# beatrix_A_v1.net
KiCad netlist of a schematic drawn in EAGLE
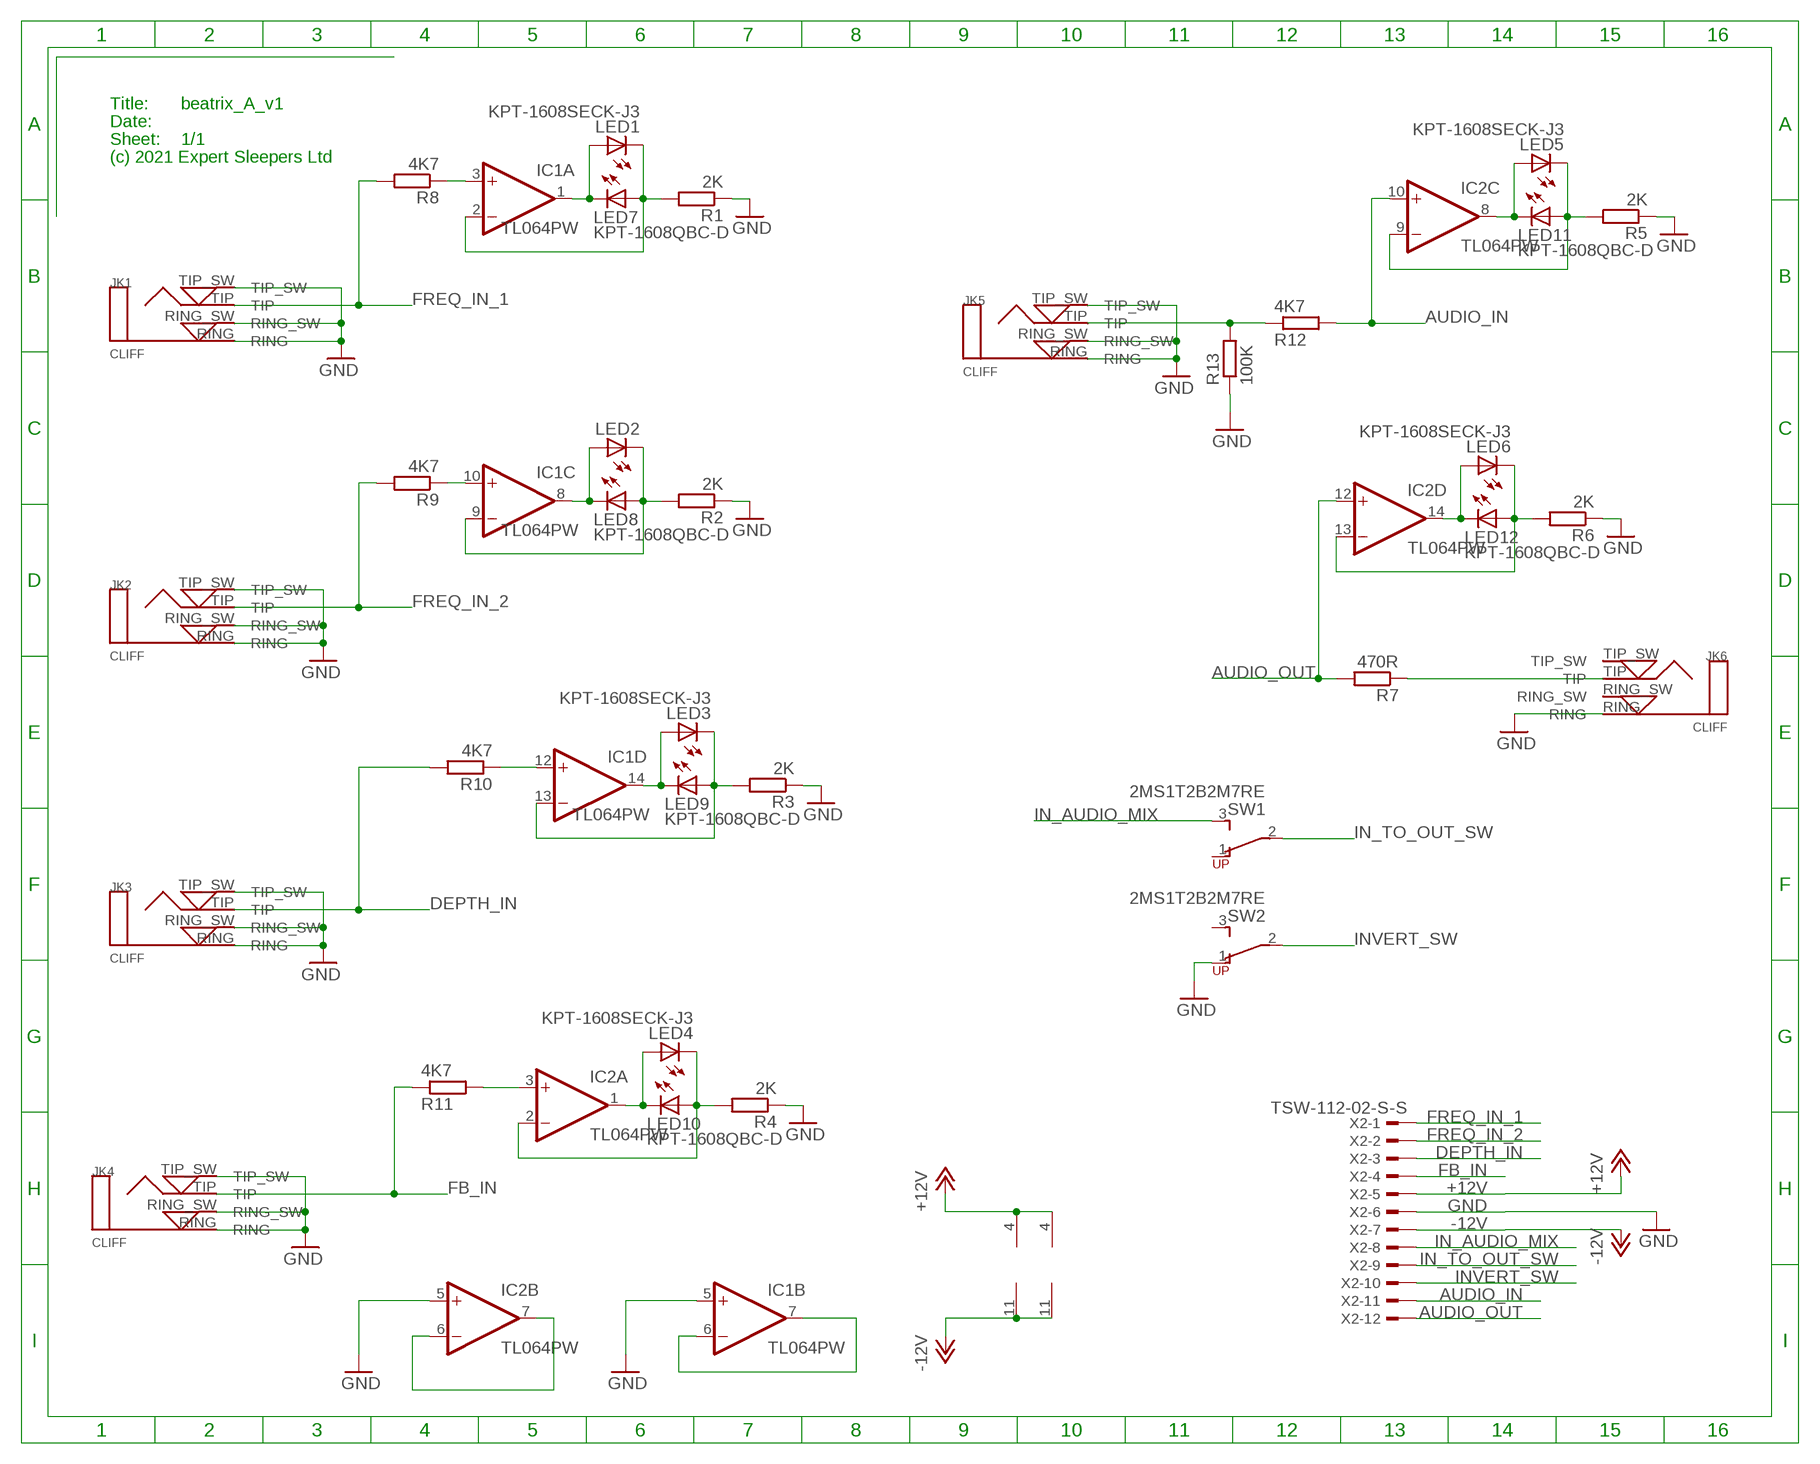
[diagram p0: schematic, sheet 1]

(export (version "E")
  (design (tool "Eeschema 10.0.6"))
  (components
    (comp (ref "IC1")
      (value "TL064PW")
      (footprint "eagle-import:PW_R-PDSO-G14")
      (libsource (lib "eagle-import") (part "TL074PW"))
    )
    (comp (ref "IC2")
      (value "TL064PW")
      (footprint "eagle-import:PW_R-PDSO-G14")
      (libsource (lib "eagle-import") (part "TL074PW"))
    )
    (comp (ref "JK1")
      (value "CLIFF")
      (footprint "eagle-import:CLIFF3.5MMPCB")
      (libsource (lib "eagle-import") (part "CLIFF3.5MM_PCB_SW_JK"))
    )
    (comp (ref "JK2")
      (value "CLIFF")
      (footprint "eagle-import:CLIFF3.5MMPCB")
      (libsource (lib "eagle-import") (part "CLIFF3.5MM_PCB_SW_JK"))
    )
    (comp (ref "JK3")
      (value "CLIFF")
      (footprint "eagle-import:CLIFF3.5MMPCB")
      (libsource (lib "eagle-import") (part "CLIFF3.5MM_PCB_SW_JK"))
    )
    (comp (ref "JK4")
      (value "CLIFF")
      (footprint "eagle-import:CLIFF3.5MMPCB")
      (libsource (lib "eagle-import") (part "CLIFF3.5MM_PCB_SW_JK"))
    )
    (comp (ref "JK5")
      (value "CLIFF")
      (footprint "eagle-import:CLIFF3.5MMPCB")
      (libsource (lib "eagle-import") (part "CLIFF3.5MM_PCB_SW_JK"))
    )
    (comp (ref "JK6")
      (value "CLIFF")
      (footprint "eagle-import:CLIFF3.5MMPCB")
      (libsource (lib "eagle-import") (part "CLIFF3.5MM_PCB_SW_JK"))
    )
    (comp (ref "LED1")
      (value "KPT-1608SECK-J3")
      (footprint "eagle-import:CHIPLED_0603_LEFT")
      (libsource (lib "eagle-import") (part "KPT-1608SECK-J3"))
    )
    (comp (ref "LED2")
      (value "KPT-1608SECK-J3")
      (footprint "eagle-import:CHIPLED_0603_LEFT")
      (libsource (lib "eagle-import") (part "KPT-1608SECK-J3"))
    )
    (comp (ref "LED3")
      (value "KPT-1608SECK-J3")
      (footprint "eagle-import:CHIPLED_0603_LEFT")
      (libsource (lib "eagle-import") (part "KPT-1608SECK-J3"))
    )
    (comp (ref "LED4")
      (value "KPT-1608SECK-J3")
      (footprint "eagle-import:CHIPLED_0603_LEFT")
      (libsource (lib "eagle-import") (part "KPT-1608SECK-J3"))
    )
    (comp (ref "LED5")
      (value "KPT-1608SECK-J3")
      (footprint "eagle-import:CHIPLED_0603_LEFT")
      (libsource (lib "eagle-import") (part "KPT-1608SECK-J3"))
    )
    (comp (ref "LED6")
      (value "KPT-1608SECK-J3")
      (footprint "eagle-import:CHIPLED_0603_LEFT")
      (libsource (lib "eagle-import") (part "KPT-1608SECK-J3"))
    )
    (comp (ref "LED7")
      (value "KPT-1608QBC-D")
      (footprint "eagle-import:CHIPLED_0603_RIGHT")
      (libsource (lib "eagle-import") (part "KPT-1608QBC-D"))
    )
    (comp (ref "LED8")
      (value "KPT-1608QBC-D")
      (footprint "eagle-import:CHIPLED_0603_RIGHT")
      (libsource (lib "eagle-import") (part "KPT-1608QBC-D"))
    )
    (comp (ref "LED9")
      (value "KPT-1608QBC-D")
      (footprint "eagle-import:CHIPLED_0603_RIGHT")
      (libsource (lib "eagle-import") (part "KPT-1608QBC-D"))
    )
    (comp (ref "LED10")
      (value "KPT-1608QBC-D")
      (footprint "eagle-import:CHIPLED_0603_RIGHT")
      (libsource (lib "eagle-import") (part "KPT-1608QBC-D"))
    )
    (comp (ref "LED11")
      (value "KPT-1608QBC-D")
      (footprint "eagle-import:CHIPLED_0603_RIGHT")
      (libsource (lib "eagle-import") (part "KPT-1608QBC-D"))
    )
    (comp (ref "LED12")
      (value "KPT-1608QBC-D")
      (footprint "eagle-import:CHIPLED_0603_RIGHT")
      (libsource (lib "eagle-import") (part "KPT-1608QBC-D"))
    )
    (comp (ref "R1")
      (value "2K")
      (footprint "eagle-import:R1206")
      (libsource (lib "eagle-import") (part "R-EU_R1206"))
    )
    (comp (ref "R2")
      (value "2K")
      (footprint "eagle-import:R1206")
      (libsource (lib "eagle-import") (part "R-EU_R1206"))
    )
    (comp (ref "R3")
      (value "2K")
      (footprint "eagle-import:R1206")
      (libsource (lib "eagle-import") (part "R-EU_R1206"))
    )
    (comp (ref "R4")
      (value "2K")
      (footprint "eagle-import:R1206")
      (libsource (lib "eagle-import") (part "R-EU_R1206"))
    )
    (comp (ref "R5")
      (value "2K")
      (footprint "eagle-import:R1206")
      (libsource (lib "eagle-import") (part "R-EU_R1206"))
    )
    (comp (ref "R6")
      (value "2K")
      (footprint "eagle-import:R1206")
      (libsource (lib "eagle-import") (part "R-EU_R1206"))
    )
    (comp (ref "R7")
      (value "470R")
      (footprint "eagle-import:R1206")
      (libsource (lib "eagle-import") (part "R-EU_R1206"))
    )
    (comp (ref "R8")
      (value "4K7")
      (footprint "eagle-import:R1206")
      (libsource (lib "eagle-import") (part "R-EU_R1206"))
    )
    (comp (ref "R9")
      (value "4K7")
      (footprint "eagle-import:R1206")
      (libsource (lib "eagle-import") (part "R-EU_R1206"))
    )
    (comp (ref "R10")
      (value "4K7")
      (footprint "eagle-import:R1206")
      (libsource (lib "eagle-import") (part "R-EU_R1206"))
    )
    (comp (ref "R11")
      (value "4K7")
      (footprint "eagle-import:R1206")
      (libsource (lib "eagle-import") (part "R-EU_R1206"))
    )
    (comp (ref "R12")
      (value "4K7")
      (footprint "eagle-import:R1206")
      (libsource (lib "eagle-import") (part "R-EU_R1206"))
    )
    (comp (ref "R13")
      (value "100K")
      (footprint "eagle-import:R0603")
      (libsource (lib "eagle-import") (part "R-EU_R0603"))
    )
    (comp (ref "SW1")
      (value "2MS1T2B2M7RE")
      (footprint "eagle-import:2MS1T2B2M7RE")
      (libsource (lib "eagle-import") (part "2MS1T2B2M7RE"))
    )
    (comp (ref "SW2")
      (value "2MS1T2B2M7RE")
      (footprint "eagle-import:2MS1T2B2M7RE")
      (libsource (lib "eagle-import") (part "2MS1T2B2M7RE"))
    )
    (comp (ref "X2")
      (value "TSW-112-02-S-S")
      (footprint "eagle-import:TSW-112-02-S-S")
      (libsource (lib "eagle-import") (part "TSW-112-02-S-S"))
    )
  )
  (nets
    (net (code "1") (name "+12V") (class "Default")
      (node (ref "IC1") (pin "4") (pinfunction "V+_4") (pintype "power_in"))
      (node (ref "IC2") (pin "4") (pinfunction "V+_4") (pintype "power_in"))
      (node (ref "X2") (pin "5") (pinfunction "1_5") (pintype "passive"))
    )
    (net (code "2") (name "-12V") (class "Default")
      (node (ref "IC1") (pin "11") (pinfunction "V-_11") (pintype "power_in"))
      (node (ref "IC2") (pin "11") (pinfunction "V-_11") (pintype "power_in"))
      (node (ref "X2") (pin "7") (pinfunction "1_7") (pintype "passive"))
    )
    (net (code "3") (name "/AUDIO_IN") (class "Default")
      (node (ref "IC2") (pin "10") (pinfunction "+IN_10") (pintype "input"))
      (node (ref "R12") (pin "2") (pinfunction "2_2") (pintype "passive"))
      (node (ref "X2") (pin "11") (pinfunction "1_11") (pintype "passive"))
    )
    (net (code "4") (name "/AUDIO_OUT") (class "Default")
      (node (ref "IC2") (pin "12") (pinfunction "+IN_12") (pintype "input"))
      (node (ref "R7") (pin "2") (pinfunction "2_2") (pintype "passive"))
      (node (ref "X2") (pin "12") (pinfunction "1_12") (pintype "passive"))
    )
    (net (code "5") (name "/DEPTH_IN") (class "Default")
      (node (ref "JK3") (pin "TIP") (pinfunction "TIP_TIP") (pintype "bidirectional"))
      (node (ref "R10") (pin "2") (pinfunction "2_2") (pintype "passive"))
      (node (ref "X2") (pin "3") (pinfunction "1_3") (pintype "passive"))
    )
    (net (code "6") (name "/FB_IN") (class "Default")
      (node (ref "JK4") (pin "TIP") (pinfunction "TIP_TIP") (pintype "bidirectional"))
      (node (ref "R11") (pin "1") (pinfunction "1_1") (pintype "passive"))
      (node (ref "X2") (pin "4") (pinfunction "1_4") (pintype "passive"))
    )
    (net (code "7") (name "/FREQ_IN_1") (class "Default")
      (node (ref "JK1") (pin "TIP") (pinfunction "TIP_TIP") (pintype "bidirectional"))
      (node (ref "R8") (pin "2") (pinfunction "2_2") (pintype "passive"))
      (node (ref "X2") (pin "1") (pinfunction "1_1") (pintype "passive"))
    )
    (net (code "8") (name "/FREQ_IN_2") (class "Default")
      (node (ref "JK2") (pin "TIP") (pinfunction "TIP_TIP") (pintype "bidirectional"))
      (node (ref "R9") (pin "2") (pinfunction "2_2") (pintype "passive"))
      (node (ref "X2") (pin "2") (pinfunction "1_2") (pintype "passive"))
    )
    (net (code "9") (name "/INVERT_SW") (class "Default")
      (node (ref "SW2") (pin "2") (pinfunction "PR_2") (pintype "passive"))
      (node (ref "X2") (pin "10") (pinfunction "1_10") (pintype "passive"))
    )
    (net (code "10") (name "/IN_AUDIO_MIX") (class "Default")
      (node (ref "SW1") (pin "3") (pinfunction "RD_3") (pintype "passive"))
      (node (ref "X2") (pin "8") (pinfunction "1_8") (pintype "passive"))
    )
    (net (code "11") (name "/IN_TO_OUT_SW") (class "Default")
      (node (ref "SW1") (pin "2") (pinfunction "PR_2") (pintype "passive"))
      (node (ref "X2") (pin "9") (pinfunction "1_9") (pintype "passive"))
    )
    (net (code "12") (name "GND") (class "Default")
      (node (ref "IC1") (pin "5") (pinfunction "+IN_5") (pintype "input"))
      (node (ref "IC2") (pin "5") (pinfunction "+IN_5") (pintype "input"))
      (node (ref "JK1") (pin "RING") (pinfunction "RING_RING") (pintype "bidirectional"))
      (node (ref "JK1") (pin "RING_SW") (pinfunction "RING_SW_RING_SW") (pintype "bidirectional"))
      (node (ref "JK1") (pin "TIP_SW") (pinfunction "TIP_SW_TIP_SW") (pintype "bidirectional"))
      (node (ref "JK2") (pin "RING") (pinfunction "RING_RING") (pintype "bidirectional"))
      (node (ref "JK2") (pin "RING_SW") (pinfunction "RING_SW_RING_SW") (pintype "bidirectional"))
      (node (ref "JK2") (pin "TIP_SW") (pinfunction "TIP_SW_TIP_SW") (pintype "bidirectional"))
      (node (ref "JK3") (pin "RING") (pinfunction "RING_RING") (pintype "bidirectional"))
      (node (ref "JK3") (pin "RING_SW") (pinfunction "RING_SW_RING_SW") (pintype "bidirectional"))
      (node (ref "JK3") (pin "TIP_SW") (pinfunction "TIP_SW_TIP_SW") (pintype "bidirectional"))
      (node (ref "JK4") (pin "RING") (pinfunction "RING_RING") (pintype "bidirectional"))
      (node (ref "JK4") (pin "RING_SW") (pinfunction "RING_SW_RING_SW") (pintype "bidirectional"))
      (node (ref "JK4") (pin "TIP_SW") (pinfunction "TIP_SW_TIP_SW") (pintype "bidirectional"))
      (node (ref "JK5") (pin "RING") (pinfunction "RING_RING") (pintype "bidirectional"))
      (node (ref "JK5") (pin "RING_SW") (pinfunction "RING_SW_RING_SW") (pintype "bidirectional"))
      (node (ref "JK5") (pin "TIP_SW") (pinfunction "TIP_SW_TIP_SW") (pintype "bidirectional"))
      (node (ref "JK6") (pin "RING") (pinfunction "RING_RING") (pintype "bidirectional"))
      (node (ref "R1") (pin "1") (pinfunction "1_1") (pintype "passive"))
      (node (ref "R13") (pin "1") (pinfunction "1_1") (pintype "passive"))
      (node (ref "R2") (pin "1") (pinfunction "1_1") (pintype "passive"))
      (node (ref "R3") (pin "1") (pinfunction "1_1") (pintype "passive"))
      (node (ref "R4") (pin "1") (pinfunction "1_1") (pintype "passive"))
      (node (ref "R5") (pin "1") (pinfunction "1_1") (pintype "passive"))
      (node (ref "R6") (pin "1") (pinfunction "1_1") (pintype "passive"))
      (node (ref "SW2") (pin "1") (pinfunction "RU_1") (pintype "passive"))
      (node (ref "X2") (pin "6") (pinfunction "1_6") (pintype "passive"))
    )
    (net (code "13") (name "Net-(IC1A-+IN)") (class "Default")
      (node (ref "IC1") (pin "3") (pinfunction "+IN_3") (pintype "input"))
      (node (ref "R8") (pin "1") (pinfunction "1_1") (pintype "passive"))
    )
    (net (code "14") (name "Net-(IC1A--IN)") (class "Default")
      (node (ref "IC1") (pin "2") (pinfunction "-IN_2") (pintype "input"))
      (node (ref "LED1") (pin "1") (pinfunction "C_1") (pintype "passive"))
      (node (ref "LED7") (pin "1") (pinfunction "A_1") (pintype "passive"))
      (node (ref "R1") (pin "2") (pinfunction "2_2") (pintype "passive"))
    )
    (net (code "15") (name "Net-(IC1A-OUT)") (class "Default")
      (node (ref "IC1") (pin "1") (pinfunction "OUT_1") (pintype "output"))
      (node (ref "LED1") (pin "2") (pinfunction "A_2") (pintype "passive"))
      (node (ref "LED7") (pin "2") (pinfunction "C_2") (pintype "passive"))
    )
    (net (code "16") (name "Net-(IC1B--IN)") (class "Default")
      (node (ref "IC1") (pin "6") (pinfunction "-IN_6") (pintype "input"))
      (node (ref "IC1") (pin "7") (pinfunction "OUT_7") (pintype "output"))
    )
    (net (code "17") (name "Net-(IC1C-+IN)") (class "Default")
      (node (ref "IC1") (pin "10") (pinfunction "+IN_10") (pintype "input"))
      (node (ref "R9") (pin "1") (pinfunction "1_1") (pintype "passive"))
    )
    (net (code "18") (name "Net-(IC1C--IN)") (class "Default")
      (node (ref "IC1") (pin "9") (pinfunction "-IN_9") (pintype "input"))
      (node (ref "LED2") (pin "1") (pinfunction "C_1") (pintype "passive"))
      (node (ref "LED8") (pin "1") (pinfunction "A_1") (pintype "passive"))
      (node (ref "R2") (pin "2") (pinfunction "2_2") (pintype "passive"))
    )
    (net (code "19") (name "Net-(IC1C-OUT)") (class "Default")
      (node (ref "IC1") (pin "8") (pinfunction "OUT_8") (pintype "output"))
      (node (ref "LED2") (pin "2") (pinfunction "A_2") (pintype "passive"))
      (node (ref "LED8") (pin "2") (pinfunction "C_2") (pintype "passive"))
    )
    (net (code "20") (name "Net-(IC1D-+IN)") (class "Default")
      (node (ref "IC1") (pin "12") (pinfunction "+IN_12") (pintype "input"))
      (node (ref "R10") (pin "1") (pinfunction "1_1") (pintype "passive"))
    )
    (net (code "21") (name "Net-(IC1D--IN)") (class "Default")
      (node (ref "IC1") (pin "13") (pinfunction "-IN_13") (pintype "input"))
      (node (ref "LED3") (pin "1") (pinfunction "C_1") (pintype "passive"))
      (node (ref "LED9") (pin "1") (pinfunction "A_1") (pintype "passive"))
      (node (ref "R3") (pin "2") (pinfunction "2_2") (pintype "passive"))
    )
    (net (code "22") (name "Net-(IC1D-OUT)") (class "Default")
      (node (ref "IC1") (pin "14") (pinfunction "OUT_14") (pintype "output"))
      (node (ref "LED3") (pin "2") (pinfunction "A_2") (pintype "passive"))
      (node (ref "LED9") (pin "2") (pinfunction "C_2") (pintype "passive"))
    )
    (net (code "23") (name "Net-(IC2A-+IN)") (class "Default")
      (node (ref "IC2") (pin "3") (pinfunction "+IN_3") (pintype "input"))
      (node (ref "R11") (pin "2") (pinfunction "2_2") (pintype "passive"))
    )
    (net (code "24") (name "Net-(IC2A--IN)") (class "Default")
      (node (ref "IC2") (pin "2") (pinfunction "-IN_2") (pintype "input"))
      (node (ref "LED10") (pin "1") (pinfunction "A_1") (pintype "passive"))
      (node (ref "LED4") (pin "1") (pinfunction "C_1") (pintype "passive"))
      (node (ref "R4") (pin "2") (pinfunction "2_2") (pintype "passive"))
    )
    (net (code "25") (name "Net-(IC2A-OUT)") (class "Default")
      (node (ref "IC2") (pin "1") (pinfunction "OUT_1") (pintype "output"))
      (node (ref "LED10") (pin "2") (pinfunction "C_2") (pintype "passive"))
      (node (ref "LED4") (pin "2") (pinfunction "A_2") (pintype "passive"))
    )
    (net (code "26") (name "Net-(IC2B--IN)") (class "Default")
      (node (ref "IC2") (pin "6") (pinfunction "-IN_6") (pintype "input"))
      (node (ref "IC2") (pin "7") (pinfunction "OUT_7") (pintype "output"))
    )
    (net (code "27") (name "Net-(IC2C--IN)") (class "Default")
      (node (ref "IC2") (pin "9") (pinfunction "-IN_9") (pintype "input"))
      (node (ref "LED11") (pin "1") (pinfunction "A_1") (pintype "passive"))
      (node (ref "LED5") (pin "1") (pinfunction "C_1") (pintype "passive"))
      (node (ref "R5") (pin "2") (pinfunction "2_2") (pintype "passive"))
    )
    (net (code "28") (name "Net-(IC2C-OUT)") (class "Default")
      (node (ref "IC2") (pin "8") (pinfunction "OUT_8") (pintype "output"))
      (node (ref "LED11") (pin "2") (pinfunction "C_2") (pintype "passive"))
      (node (ref "LED5") (pin "2") (pinfunction "A_2") (pintype "passive"))
    )
    (net (code "29") (name "Net-(IC2D--IN)") (class "Default")
      (node (ref "IC2") (pin "13") (pinfunction "-IN_13") (pintype "input"))
      (node (ref "LED12") (pin "1") (pinfunction "A_1") (pintype "passive"))
      (node (ref "LED6") (pin "1") (pinfunction "C_1") (pintype "passive"))
      (node (ref "R6") (pin "2") (pinfunction "2_2") (pintype "passive"))
    )
    (net (code "30") (name "Net-(IC2D-OUT)") (class "Default")
      (node (ref "IC2") (pin "14") (pinfunction "OUT_14") (pintype "output"))
      (node (ref "LED12") (pin "2") (pinfunction "C_2") (pintype "passive"))
      (node (ref "LED6") (pin "2") (pinfunction "A_2") (pintype "passive"))
    )
    (net (code "31") (name "Net-(JK5-PadTIP)") (class "Default")
      (node (ref "JK5") (pin "TIP") (pinfunction "TIP_TIP") (pintype "bidirectional"))
      (node (ref "R12") (pin "1") (pinfunction "1_1") (pintype "passive"))
      (node (ref "R13") (pin "2") (pinfunction "2_2") (pintype "passive"))
    )
    (net (code "32") (name "Net-(JK6-PadTIP)") (class "Default")
      (node (ref "JK6") (pin "TIP") (pinfunction "TIP_TIP") (pintype "bidirectional"))
      (node (ref "R7") (pin "1") (pinfunction "1_1") (pintype "passive"))
    )
    (net (code "33") (name "unconnected-(JK6-PadRING_SW)") (class "Default")
      (node (ref "JK6") (pin "RING_SW") (pinfunction "RING_SW_RING_SW") (pintype "bidirectional"))
    )
    (net (code "34") (name "unconnected-(JK6-PadTIP_SW)") (class "Default")
      (node (ref "JK6") (pin "TIP_SW") (pinfunction "TIP_SW_TIP_SW") (pintype "bidirectional"))
    )
    (net (code "35") (name "unconnected-(SW1-RU-Pad1)") (class "Default")
      (node (ref "SW1") (pin "1") (pinfunction "RU_1") (pintype "passive"))
    )
    (net (code "36") (name "unconnected-(SW2-RD-Pad3)") (class "Default")
      (node (ref "SW2") (pin "3") (pinfunction "RD_3") (pintype "passive"))
    )
  )
)
